# brakeBoard.net
KiCad netlist of a schematic drawn in EAGLE
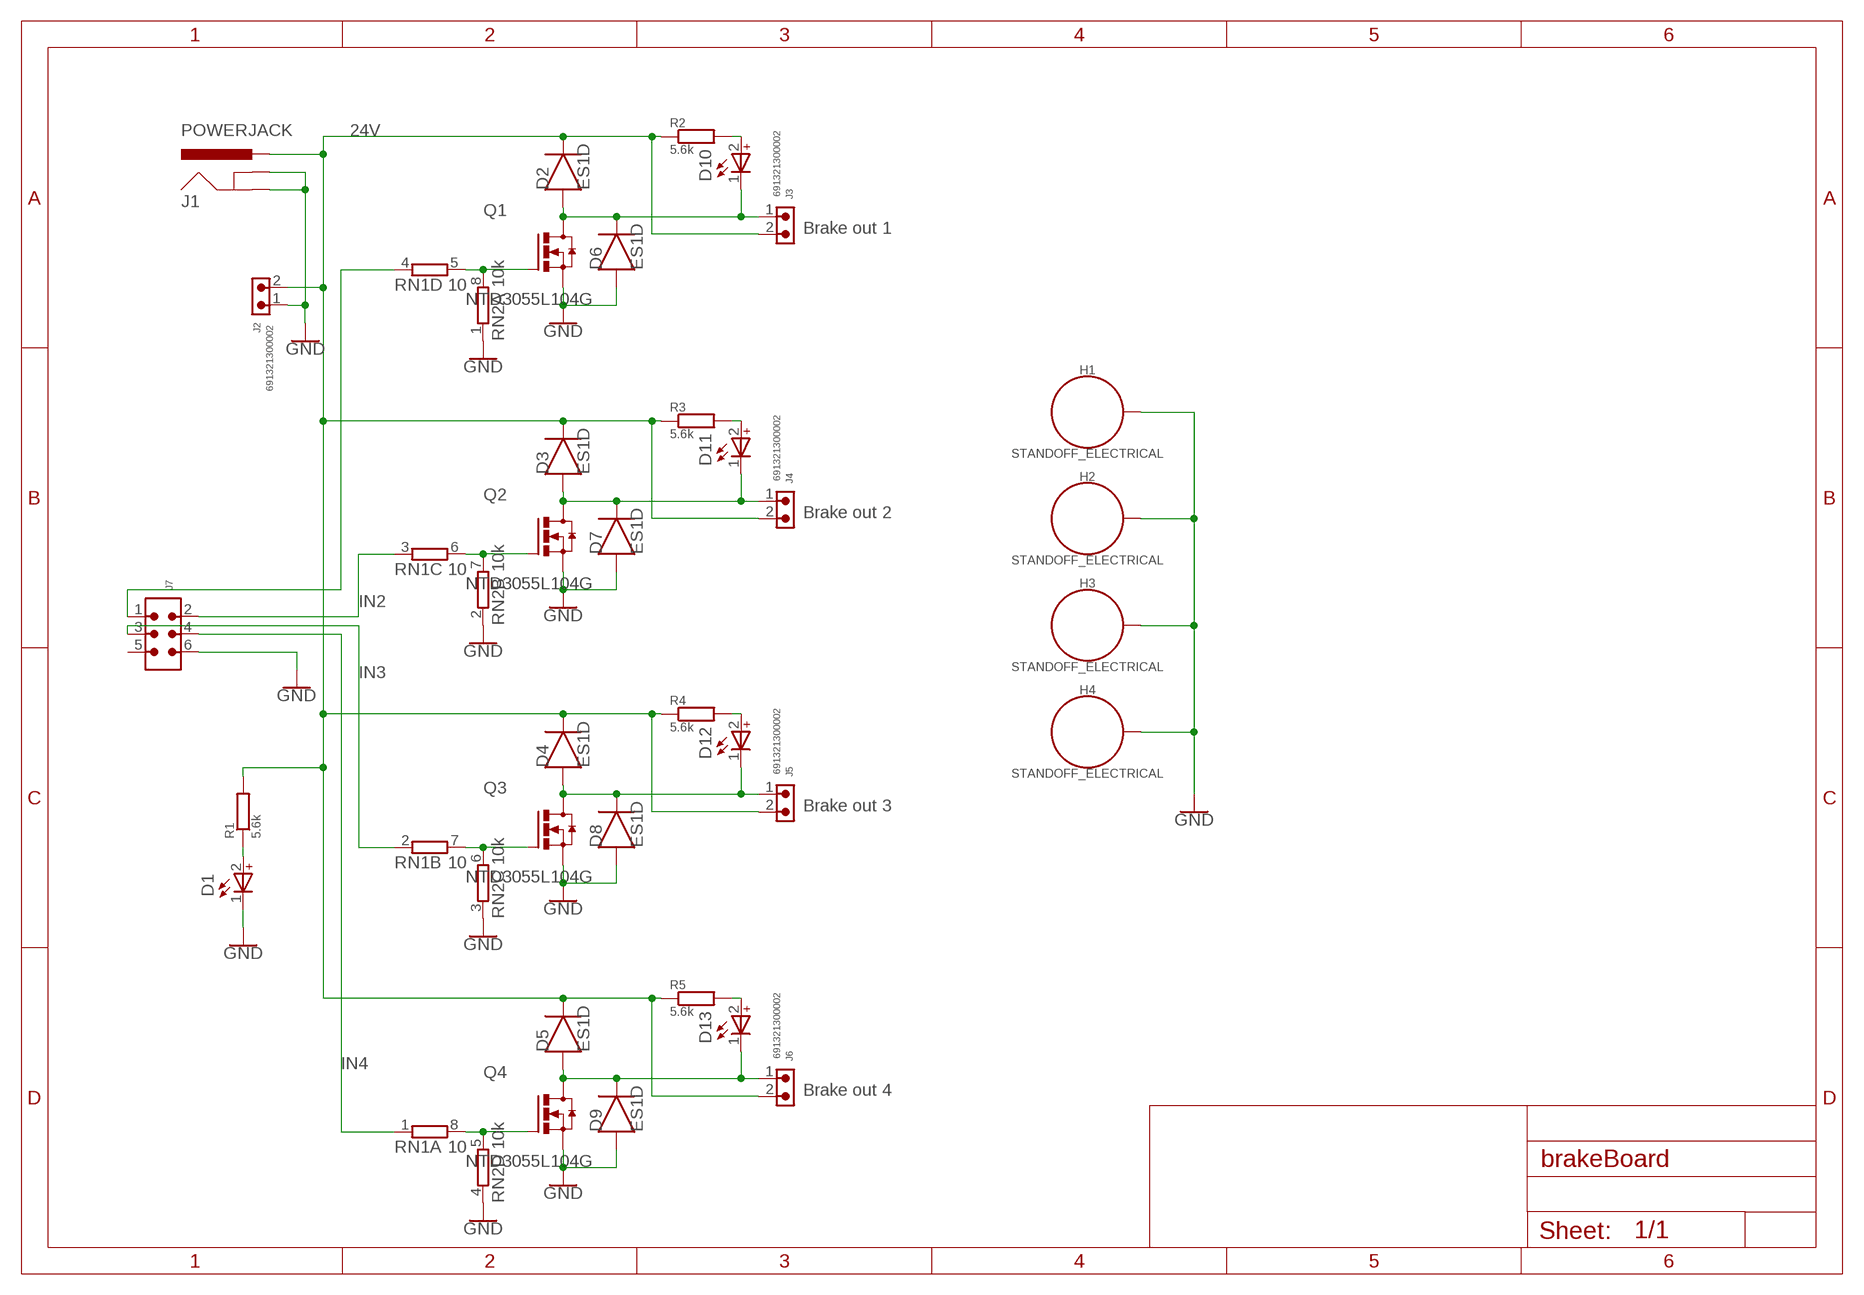
[diagram p0: schematic, sheet 1]

(export (version "E")
  (design (tool "Eeschema 10.0.6"))
  (components
    (comp (ref "D1")
      (value "WL-SMCD_0603_150060GS55040")
      (footprint "eagle-import:WL-SMCD_0603")
      (libsource (lib "eagle-import") (part "WL-SMCD_0603_150060GS55040"))
    )
    (comp (ref "D2")
      (value "ES1D")
      (footprint "eagle-import:DIOM5226X290N")
      (fields (field (name "MANUFACTURER") "ON Semiconductor "))
      (libsource (lib "eagle-import") (part "DIODE__SMAES1D"))
    )
    (comp (ref "D3")
      (value "ES1D")
      (footprint "eagle-import:DIOM5226X290N")
      (fields (field (name "MANUFACTURER") "ON Semiconductor "))
      (libsource (lib "eagle-import") (part "DIODE__SMAES1D"))
    )
    (comp (ref "D4")
      (value "ES1D")
      (footprint "eagle-import:DIOM5226X290N")
      (fields (field (name "MANUFACTURER") "ON Semiconductor "))
      (libsource (lib "eagle-import") (part "DIODE__SMAES1D"))
    )
    (comp (ref "D5")
      (value "ES1D")
      (footprint "eagle-import:DIOM5226X290N")
      (fields (field (name "MANUFACTURER") "ON Semiconductor "))
      (libsource (lib "eagle-import") (part "DIODE__SMAES1D"))
    )
    (comp (ref "D6")
      (value "ES1D")
      (footprint "eagle-import:DIOM5226X290N")
      (fields (field (name "MANUFACTURER") "ON Semiconductor "))
      (libsource (lib "eagle-import") (part "DIODE__SMAES1D"))
    )
    (comp (ref "D7")
      (value "ES1D")
      (footprint "eagle-import:DIOM5226X290N")
      (fields (field (name "MANUFACTURER") "ON Semiconductor "))
      (libsource (lib "eagle-import") (part "DIODE__SMAES1D"))
    )
    (comp (ref "D8")
      (value "ES1D")
      (footprint "eagle-import:DIOM5226X290N")
      (fields (field (name "MANUFACTURER") "ON Semiconductor "))
      (libsource (lib "eagle-import") (part "DIODE__SMAES1D"))
    )
    (comp (ref "D9")
      (value "ES1D")
      (footprint "eagle-import:DIOM5226X290N")
      (fields (field (name "MANUFACTURER") "ON Semiconductor "))
      (libsource (lib "eagle-import") (part "DIODE__SMAES1D"))
    )
    (comp (ref "D10")
      (value "WL-SMCD_0603_150060GS55040")
      (footprint "eagle-import:WL-SMCD_0603")
      (libsource (lib "eagle-import") (part "WL-SMCD_0603_150060GS55040"))
    )
    (comp (ref "D11")
      (value "WL-SMCD_0603_150060GS55040")
      (footprint "eagle-import:WL-SMCD_0603")
      (libsource (lib "eagle-import") (part "WL-SMCD_0603_150060GS55040"))
    )
    (comp (ref "D12")
      (value "WL-SMCD_0603_150060GS55040")
      (footprint "eagle-import:WL-SMCD_0603")
      (libsource (lib "eagle-import") (part "WL-SMCD_0603_150060GS55040"))
    )
    (comp (ref "D13")
      (value "WL-SMCD_0603_150060GS55040")
      (footprint "eagle-import:WL-SMCD_0603")
      (libsource (lib "eagle-import") (part "WL-SMCD_0603_150060GS55040"))
    )
    (comp (ref "H1")
      (value "STANDOFF_ELECTRICAL")
      (footprint "eagle-import:STANDOFF-ELECTRICAL")
      (libsource (lib "eagle-import") (part "STANDOFF_ELECTRICAL"))
    )
    (comp (ref "H2")
      (value "STANDOFF_ELECTRICAL")
      (footprint "eagle-import:STANDOFF-ELECTRICAL")
      (libsource (lib "eagle-import") (part "STANDOFF_ELECTRICAL"))
    )
    (comp (ref "H3")
      (value "STANDOFF_ELECTRICAL")
      (footprint "eagle-import:STANDOFF-ELECTRICAL")
      (libsource (lib "eagle-import") (part "STANDOFF_ELECTRICAL"))
    )
    (comp (ref "H4")
      (value "STANDOFF_ELECTRICAL")
      (footprint "eagle-import:STANDOFF-ELECTRICAL")
      (libsource (lib "eagle-import") (part "STANDOFF_ELECTRICAL"))
    )
    (comp (ref "J1")
      (value "POWERJACK")
      (footprint "eagle-import:POWERJACK_SLOT")
      (libsource (lib "eagle-import") (part "POWERJACK"))
    )
    (comp (ref "J2")
      (value "691321300002")
      (footprint "eagle-import:691321300002")
      (libsource (lib "eagle-import") (part "691321300002"))
    )
    (comp (ref "J3")
      (value "691321300002")
      (footprint "eagle-import:691321300002")
      (libsource (lib "eagle-import") (part "691321300002"))
    )
    (comp (ref "J4")
      (value "691321300002")
      (footprint "eagle-import:691321300002")
      (libsource (lib "eagle-import") (part "691321300002"))
    )
    (comp (ref "J5")
      (value "691321300002")
      (footprint "eagle-import:691321300002")
      (libsource (lib "eagle-import") (part "691321300002"))
    )
    (comp (ref "J6")
      (value "691321300002")
      (footprint "eagle-import:691321300002")
      (libsource (lib "eagle-import") (part "691321300002"))
    )
    (comp (ref "J7")
      (value "6120XX21621_61200621621")
      (footprint "eagle-import:61200621621")
      (libsource (lib "eagle-import") (part "6120XX21621_61200621621"))
    )
    (comp (ref "Q1")
      (value "NTD3055L104G")
      (footprint "eagle-import:DPAK3")
      (fields (field (name "MANUFACTURER") "ON SEMICONDUCTORS") (field (name "CREATED_BY") "PCBLayout.com"))
      (libsource (lib "eagle-import") (part "NTD3055L104G"))
    )
    (comp (ref "Q2")
      (value "NTD3055L104G")
      (footprint "eagle-import:DPAK3")
      (fields (field (name "MANUFACTURER") "ON SEMICONDUCTORS") (field (name "CREATED_BY") "PCBLayout.com"))
      (libsource (lib "eagle-import") (part "NTD3055L104G"))
    )
    (comp (ref "Q3")
      (value "NTD3055L104G")
      (footprint "eagle-import:DPAK3")
      (fields (field (name "MANUFACTURER") "ON SEMICONDUCTORS") (field (name "CREATED_BY") "PCBLayout.com"))
      (libsource (lib "eagle-import") (part "NTD3055L104G"))
    )
    (comp (ref "Q4")
      (value "NTD3055L104G")
      (footprint "eagle-import:DPAK3")
      (fields (field (name "MANUFACTURER") "ON SEMICONDUCTORS") (field (name "CREATED_BY") "PCBLayout.com"))
      (libsource (lib "eagle-import") (part "NTD3055L104G"))
    )
    (comp (ref "R1")
      (value "5.6k")
      (footprint "eagle-import:RESC2012X65")
      (libsource (lib "eagle-import") (part "RCHIP-0805(2012-METRIC)_"))
    )
    (comp (ref "R2")
      (value "5.6k")
      (footprint "eagle-import:RESC2012X65")
      (libsource (lib "eagle-import") (part "RCHIP-0805(2012-METRIC)_"))
    )
    (comp (ref "R3")
      (value "5.6k")
      (footprint "eagle-import:RESC2012X65")
      (libsource (lib "eagle-import") (part "RCHIP-0805(2012-METRIC)_"))
    )
    (comp (ref "R4")
      (value "5.6k")
      (footprint "eagle-import:RESC2012X65")
      (libsource (lib "eagle-import") (part "RCHIP-0805(2012-METRIC)_"))
    )
    (comp (ref "R5")
      (value "5.6k")
      (footprint "eagle-import:RESC2012X65")
      (libsource (lib "eagle-import") (part "RCHIP-0805(2012-METRIC)_"))
    )
    (comp (ref "RN1")
      (value "10")
      (footprint "eagle-import:CAY16_LONG_W")
      (libsource (lib "eagle-import") (part "4R-NCAY16_LONG_W"))
    )
    (comp (ref "RN2")
      (value "10k")
      (footprint "eagle-import:CAY16_LONG_W")
      (libsource (lib "eagle-import") (part "4R-NCAY16_LONG_W"))
    )
  )
  (nets
    (net (code "1") (name "/24V") (class "Default")
      (node (ref "D2") (pin "1") (pinfunction "C_1") (pintype "passive"))
      (node (ref "D3") (pin "1") (pinfunction "C_1") (pintype "passive"))
      (node (ref "D4") (pin "1") (pinfunction "C_1") (pintype "passive"))
      (node (ref "D5") (pin "1") (pinfunction "C_1") (pintype "passive"))
      (node (ref "J1") (pin "P$10") (pinfunction "PWR_P$10") (pintype "bidirectional"))
      (node (ref "J1") (pin "P$11") (pinfunction "PWR_P$11") (pintype "bidirectional"))
      (node (ref "J1") (pin "P$12") (pinfunction "PWR_P$12") (pintype "bidirectional"))
      (node (ref "J1") (pin "P$13") (pinfunction "PWR_P$13") (pintype "bidirectional"))
      (node (ref "J1") (pin "P$14") (pinfunction "PWR_P$14") (pintype "bidirectional"))
      (node (ref "J1") (pin "P$15") (pinfunction "PWR_P$15") (pintype "bidirectional"))
      (node (ref "J1") (pin "P$16") (pinfunction "PWR_P$16") (pintype "bidirectional"))
      (node (ref "J1") (pin "P$17") (pinfunction "PWR_P$17") (pintype "bidirectional"))
      (node (ref "J1") (pin "P$18") (pinfunction "PWR_P$18") (pintype "bidirectional"))
      (node (ref "J1") (pin "P$19") (pinfunction "PWR_P$19") (pintype "bidirectional"))
      (node (ref "J1") (pin "P$2") (pinfunction "PWR_P$2") (pintype "bidirectional"))
      (node (ref "J1") (pin "P$20") (pinfunction "PWR_P$20") (pintype "bidirectional"))
      (node (ref "J1") (pin "P$21") (pinfunction "PWR_P$21") (pintype "bidirectional"))
      (node (ref "J1") (pin "P$22") (pinfunction "PWR_P$22") (pintype "bidirectional"))
      (node (ref "J1") (pin "P$23") (pinfunction "PWR_P$23") (pintype "bidirectional"))
      (node (ref "J1") (pin "P$24") (pinfunction "PWR_P$24") (pintype "bidirectional"))
      (node (ref "J1") (pin "P$25") (pinfunction "PWR_P$25") (pintype "bidirectional"))
      (node (ref "J1") (pin "P$26") (pinfunction "PWR_P$26") (pintype "bidirectional"))
      (node (ref "J1") (pin "P$27") (pinfunction "PWR_P$27") (pintype "bidirectional"))
      (node (ref "J1") (pin "P$28") (pinfunction "PWR_P$28") (pintype "bidirectional"))
      (node (ref "J1") (pin "P$3") (pinfunction "PWR_P$3") (pintype "bidirectional"))
      (node (ref "J1") (pin "P$4") (pinfunction "PWR_P$4") (pintype "bidirectional"))
      (node (ref "J1") (pin "P$5") (pinfunction "PWR_P$5") (pintype "bidirectional"))
      (node (ref "J1") (pin "P$6") (pinfunction "PWR_P$6") (pintype "bidirectional"))
      (node (ref "J1") (pin "P$7") (pinfunction "PWR_P$7") (pintype "bidirectional"))
      (node (ref "J1") (pin "P$8") (pinfunction "PWR_P$8") (pintype "bidirectional"))
      (node (ref "J1") (pin "P$9") (pinfunction "PWR_P$9") (pintype "bidirectional"))
      (node (ref "J2") (pin "2") (pinfunction "2_2") (pintype "passive"))
      (node (ref "J3") (pin "2") (pinfunction "2_2") (pintype "passive"))
      (node (ref "J4") (pin "2") (pinfunction "2_2") (pintype "passive"))
      (node (ref "J5") (pin "2") (pinfunction "2_2") (pintype "passive"))
      (node (ref "J6") (pin "2") (pinfunction "2_2") (pintype "passive"))
      (node (ref "R1") (pin "2") (pinfunction "2_2") (pintype "passive"))
      (node (ref "R2") (pin "1") (pinfunction "1_1") (pintype "passive"))
      (node (ref "R3") (pin "1") (pinfunction "1_1") (pintype "passive"))
      (node (ref "R4") (pin "1") (pinfunction "1_1") (pintype "passive"))
      (node (ref "R5") (pin "1") (pinfunction "1_1") (pintype "passive"))
    )
    (net (code "2") (name "/IN2") (class "Default")
      (node (ref "J7") (pin "2") (pinfunction "2_2") (pintype "passive"))
      (node (ref "RN1") (pin "3") (pinfunction "1_3") (pintype "passive"))
    )
    (net (code "3") (name "/IN3") (class "Default")
      (node (ref "J7") (pin "3") (pinfunction "3_3") (pintype "passive"))
      (node (ref "RN1") (pin "2") (pinfunction "1_2") (pintype "passive"))
    )
    (net (code "4") (name "/IN4") (class "Default")
      (node (ref "J7") (pin "4") (pinfunction "4_4") (pintype "passive"))
      (node (ref "RN1") (pin "1") (pinfunction "1_1") (pintype "passive"))
    )
    (net (code "5") (name "GND") (class "Default")
      (node (ref "D1") (pin "1") (pinfunction "__1") (pintype "passive"))
      (node (ref "D6") (pin "2") (pinfunction "A_2") (pintype "passive"))
      (node (ref "D7") (pin "2") (pinfunction "A_2") (pintype "passive"))
      (node (ref "D8") (pin "2") (pinfunction "A_2") (pintype "passive"))
      (node (ref "D9") (pin "2") (pinfunction "A_2") (pintype "passive"))
      (node (ref "H1") (pin "P1") (pinfunction "P$1_P1") (pintype "bidirectional"))
      (node (ref "H2") (pin "P1") (pinfunction "P$1_P1") (pintype "bidirectional"))
      (node (ref "H3") (pin "P1") (pinfunction "P$1_P1") (pintype "bidirectional"))
      (node (ref "H4") (pin "P1") (pinfunction "P$1_P1") (pintype "bidirectional"))
      (node (ref "J1") (pin "P$33") (pinfunction "GNDBREAK_P$33") (pintype "bidirectional"))
      (node (ref "J1") (pin "P$34") (pinfunction "GNDBREAK_P$34") (pintype "bidirectional"))
      (node (ref "J1") (pin "P$35") (pinfunction "GNDBREAK_P$35") (pintype "bidirectional"))
      (node (ref "J1") (pin "P$36") (pinfunction "GNDBREAK_P$36") (pintype "bidirectional"))
      (node (ref "J1") (pin "P$37") (pinfunction "GNDBREAK_P$37") (pintype "bidirectional"))
      (node (ref "J1") (pin "P$38") (pinfunction "GNDBREAK_P$38") (pintype "bidirectional"))
      (node (ref "J1") (pin "P$39") (pinfunction "GNDBREAK_P$39") (pintype "bidirectional"))
      (node (ref "J1") (pin "P$40") (pinfunction "GNDBREAK_P$40") (pintype "bidirectional"))
      (node (ref "J1") (pin "P$41") (pinfunction "GNDBREAK_P$41") (pintype "bidirectional"))
      (node (ref "J1") (pin "P$42") (pinfunction "GNDBREAK_P$42") (pintype "bidirectional"))
      (node (ref "J1") (pin "P$43") (pinfunction "GNDBREAK_P$43") (pintype "bidirectional"))
      (node (ref "J1") (pin "P$44") (pinfunction "GNDBREAK_P$44") (pintype "bidirectional"))
      (node (ref "J1") (pin "P$45") (pinfunction "GNDBREAK_P$45") (pintype "bidirectional"))
      (node (ref "J1") (pin "P$46") (pinfunction "GNDBREAK_P$46") (pintype "bidirectional"))
      (node (ref "J1") (pin "P$47") (pinfunction "GNDBREAK_P$47") (pintype "bidirectional"))
      (node (ref "J1") (pin "P$48") (pinfunction "GNDBREAK_P$48") (pintype "bidirectional"))
      (node (ref "J1") (pin "P$49") (pinfunction "GNDBREAK_P$49") (pintype "bidirectional"))
      (node (ref "J1") (pin "P$50") (pinfunction "GNDBREAK_P$50") (pintype "bidirectional"))
      (node (ref "J1") (pin "P$51") (pinfunction "GNDBREAK_P$51") (pintype "bidirectional"))
      (node (ref "J1") (pin "P$52") (pinfunction "GNDBREAK_P$52") (pintype "bidirectional"))
      (node (ref "J1") (pin "P$53") (pinfunction "GNDBREAK_P$53") (pintype "bidirectional"))
      (node (ref "J1") (pin "P$54") (pinfunction "GNDBREAK_P$54") (pintype "bidirectional"))
      (node (ref "J1") (pin "P$55") (pinfunction "GNDBREAK_P$55") (pintype "bidirectional"))
      (node (ref "J1") (pin "P$56") (pinfunction "GNDBREAK_P$56") (pintype "bidirectional"))
      (node (ref "J1") (pin "P$63") (pinfunction "GND_P$63") (pintype "bidirectional"))
      (node (ref "J1") (pin "P$64") (pinfunction "GND_P$64") (pintype "bidirectional"))
      (node (ref "J1") (pin "P$65") (pinfunction "GND_P$65") (pintype "bidirectional"))
      (node (ref "J1") (pin "P$66") (pinfunction "GND_P$66") (pintype "bidirectional"))
      (node (ref "J1") (pin "P$67") (pinfunction "GND_P$67") (pintype "bidirectional"))
      (node (ref "J1") (pin "P$68") (pinfunction "GND_P$68") (pintype "bidirectional"))
      (node (ref "J1") (pin "P$69") (pinfunction "GND_P$69") (pintype "bidirectional"))
      (node (ref "J1") (pin "P$70") (pinfunction "GND_P$70") (pintype "bidirectional"))
      (node (ref "J1") (pin "P$71") (pinfunction "GND_P$71") (pintype "bidirectional"))
      (node (ref "J1") (pin "P$72") (pinfunction "GND_P$72") (pintype "bidirectional"))
      (node (ref "J1") (pin "P$73") (pinfunction "GND_P$73") (pintype "bidirectional"))
      (node (ref "J1") (pin "P$74") (pinfunction "GND_P$74") (pintype "bidirectional"))
      (node (ref "J1") (pin "P$75") (pinfunction "GND_P$75") (pintype "bidirectional"))
      (node (ref "J1") (pin "P$76") (pinfunction "GND_P$76") (pintype "bidirectional"))
      (node (ref "J1") (pin "P$77") (pinfunction "GND_P$77") (pintype "bidirectional"))
      (node (ref "J1") (pin "P$78") (pinfunction "GND_P$78") (pintype "bidirectional"))
      (node (ref "J1") (pin "P$79") (pinfunction "GND_P$79") (pintype "bidirectional"))
      (node (ref "J1") (pin "P$80") (pinfunction "GND_P$80") (pintype "bidirectional"))
      (node (ref "J1") (pin "P$81") (pinfunction "GND_P$81") (pintype "bidirectional"))
      (node (ref "J1") (pin "P$82") (pinfunction "GND_P$82") (pintype "bidirectional"))
      (node (ref "J1") (pin "P$83") (pinfunction "GND_P$83") (pintype "bidirectional"))
      (node (ref "J1") (pin "P$84") (pinfunction "GND_P$84") (pintype "bidirectional"))
      (node (ref "J1") (pin "P$85") (pinfunction "GND_P$85") (pintype "bidirectional"))
      (node (ref "J2") (pin "1") (pinfunction "1_1") (pintype "passive"))
      (node (ref "J7") (pin "6") (pinfunction "6_6") (pintype "passive"))
      (node (ref "Q1") (pin "2") (pinfunction "S_2") (pintype "passive"))
      (node (ref "Q2") (pin "2") (pinfunction "S_2") (pintype "passive"))
      (node (ref "Q3") (pin "2") (pinfunction "S_2") (pintype "passive"))
      (node (ref "Q4") (pin "2") (pinfunction "S_2") (pintype "passive"))
      (node (ref "RN2") (pin "1") (pinfunction "1_1") (pintype "passive"))
      (node (ref "RN2") (pin "2") (pinfunction "1_2") (pintype "passive"))
      (node (ref "RN2") (pin "3") (pinfunction "1_3") (pintype "passive"))
      (node (ref "RN2") (pin "4") (pinfunction "1_4") (pintype "passive"))
    )
    (net (code "6") (name "Net-(D1-+)") (class "Default")
      (node (ref "D1") (pin "2") (pinfunction "+_2") (pintype "passive"))
      (node (ref "R1") (pin "1") (pinfunction "1_1") (pintype "passive"))
    )
    (net (code "7") (name "Net-(D10-+)") (class "Default")
      (node (ref "D10") (pin "2") (pinfunction "+_2") (pintype "passive"))
      (node (ref "R2") (pin "2") (pinfunction "2_2") (pintype "passive"))
    )
    (net (code "8") (name "Net-(D10-_)") (class "Default")
      (node (ref "D10") (pin "1") (pinfunction "__1") (pintype "passive"))
      (node (ref "D2") (pin "2") (pinfunction "A_2") (pintype "passive"))
      (node (ref "D6") (pin "1") (pinfunction "C_1") (pintype "passive"))
      (node (ref "J3") (pin "1") (pinfunction "1_1") (pintype "passive"))
      (node (ref "Q1") (pin "3") (pinfunction "D_3") (pintype "passive"))
    )
    (net (code "9") (name "Net-(D11-+)") (class "Default")
      (node (ref "D11") (pin "2") (pinfunction "+_2") (pintype "passive"))
      (node (ref "R3") (pin "2") (pinfunction "2_2") (pintype "passive"))
    )
    (net (code "10") (name "Net-(D11-_)") (class "Default")
      (node (ref "D11") (pin "1") (pinfunction "__1") (pintype "passive"))
      (node (ref "D3") (pin "2") (pinfunction "A_2") (pintype "passive"))
      (node (ref "D7") (pin "1") (pinfunction "C_1") (pintype "passive"))
      (node (ref "J4") (pin "1") (pinfunction "1_1") (pintype "passive"))
      (node (ref "Q2") (pin "3") (pinfunction "D_3") (pintype "passive"))
    )
    (net (code "11") (name "Net-(D12-+)") (class "Default")
      (node (ref "D12") (pin "2") (pinfunction "+_2") (pintype "passive"))
      (node (ref "R4") (pin "2") (pinfunction "2_2") (pintype "passive"))
    )
    (net (code "12") (name "Net-(D12-_)") (class "Default")
      (node (ref "D12") (pin "1") (pinfunction "__1") (pintype "passive"))
      (node (ref "D4") (pin "2") (pinfunction "A_2") (pintype "passive"))
      (node (ref "D8") (pin "1") (pinfunction "C_1") (pintype "passive"))
      (node (ref "J5") (pin "1") (pinfunction "1_1") (pintype "passive"))
      (node (ref "Q3") (pin "3") (pinfunction "D_3") (pintype "passive"))
    )
    (net (code "13") (name "Net-(D13-+)") (class "Default")
      (node (ref "D13") (pin "2") (pinfunction "+_2") (pintype "passive"))
      (node (ref "R5") (pin "2") (pinfunction "2_2") (pintype "passive"))
    )
    (net (code "14") (name "Net-(D13-_)") (class "Default")
      (node (ref "D13") (pin "1") (pinfunction "__1") (pintype "passive"))
      (node (ref "D5") (pin "2") (pinfunction "A_2") (pintype "passive"))
      (node (ref "D9") (pin "1") (pinfunction "C_1") (pintype "passive"))
      (node (ref "J6") (pin "1") (pinfunction "1_1") (pintype "passive"))
      (node (ref "Q4") (pin "3") (pinfunction "D_3") (pintype "passive"))
    )
    (net (code "15") (name "Net-(Q1-G)") (class "Default")
      (node (ref "Q1") (pin "1") (pinfunction "G_1") (pintype "passive"))
      (node (ref "RN1") (pin "5") (pinfunction "2_5") (pintype "passive"))
      (node (ref "RN2") (pin "8") (pinfunction "2_8") (pintype "passive"))
    )
    (net (code "16") (name "Net-(Q2-G)") (class "Default")
      (node (ref "Q2") (pin "1") (pinfunction "G_1") (pintype "passive"))
      (node (ref "RN1") (pin "6") (pinfunction "2_6") (pintype "passive"))
      (node (ref "RN2") (pin "7") (pinfunction "2_7") (pintype "passive"))
    )
    (net (code "17") (name "Net-(Q3-G)") (class "Default")
      (node (ref "Q3") (pin "1") (pinfunction "G_1") (pintype "passive"))
      (node (ref "RN1") (pin "7") (pinfunction "2_7") (pintype "passive"))
      (node (ref "RN2") (pin "6") (pinfunction "2_6") (pintype "passive"))
    )
    (net (code "18") (name "Net-(Q4-G)") (class "Default")
      (node (ref "Q4") (pin "1") (pinfunction "G_1") (pintype "passive"))
      (node (ref "RN1") (pin "8") (pinfunction "2_8") (pintype "passive"))
      (node (ref "RN2") (pin "5") (pinfunction "2_5") (pintype "passive"))
    )
    (net (code "19") (name "Net-(RN1D-1)") (class "Default")
      (node (ref "J7") (pin "1") (pinfunction "1_1") (pintype "passive"))
      (node (ref "RN1") (pin "4") (pinfunction "1_4") (pintype "passive"))
    )
    (net (code "20") (name "unconnected-(J7-Pad5)") (class "Default")
      (node (ref "J7") (pin "5") (pinfunction "5_5") (pintype "passive"))
    )
  )
)
